# FPGA_Configuration_JTAG.net
KiCad netlist of a schematic drawn in Altium Designer
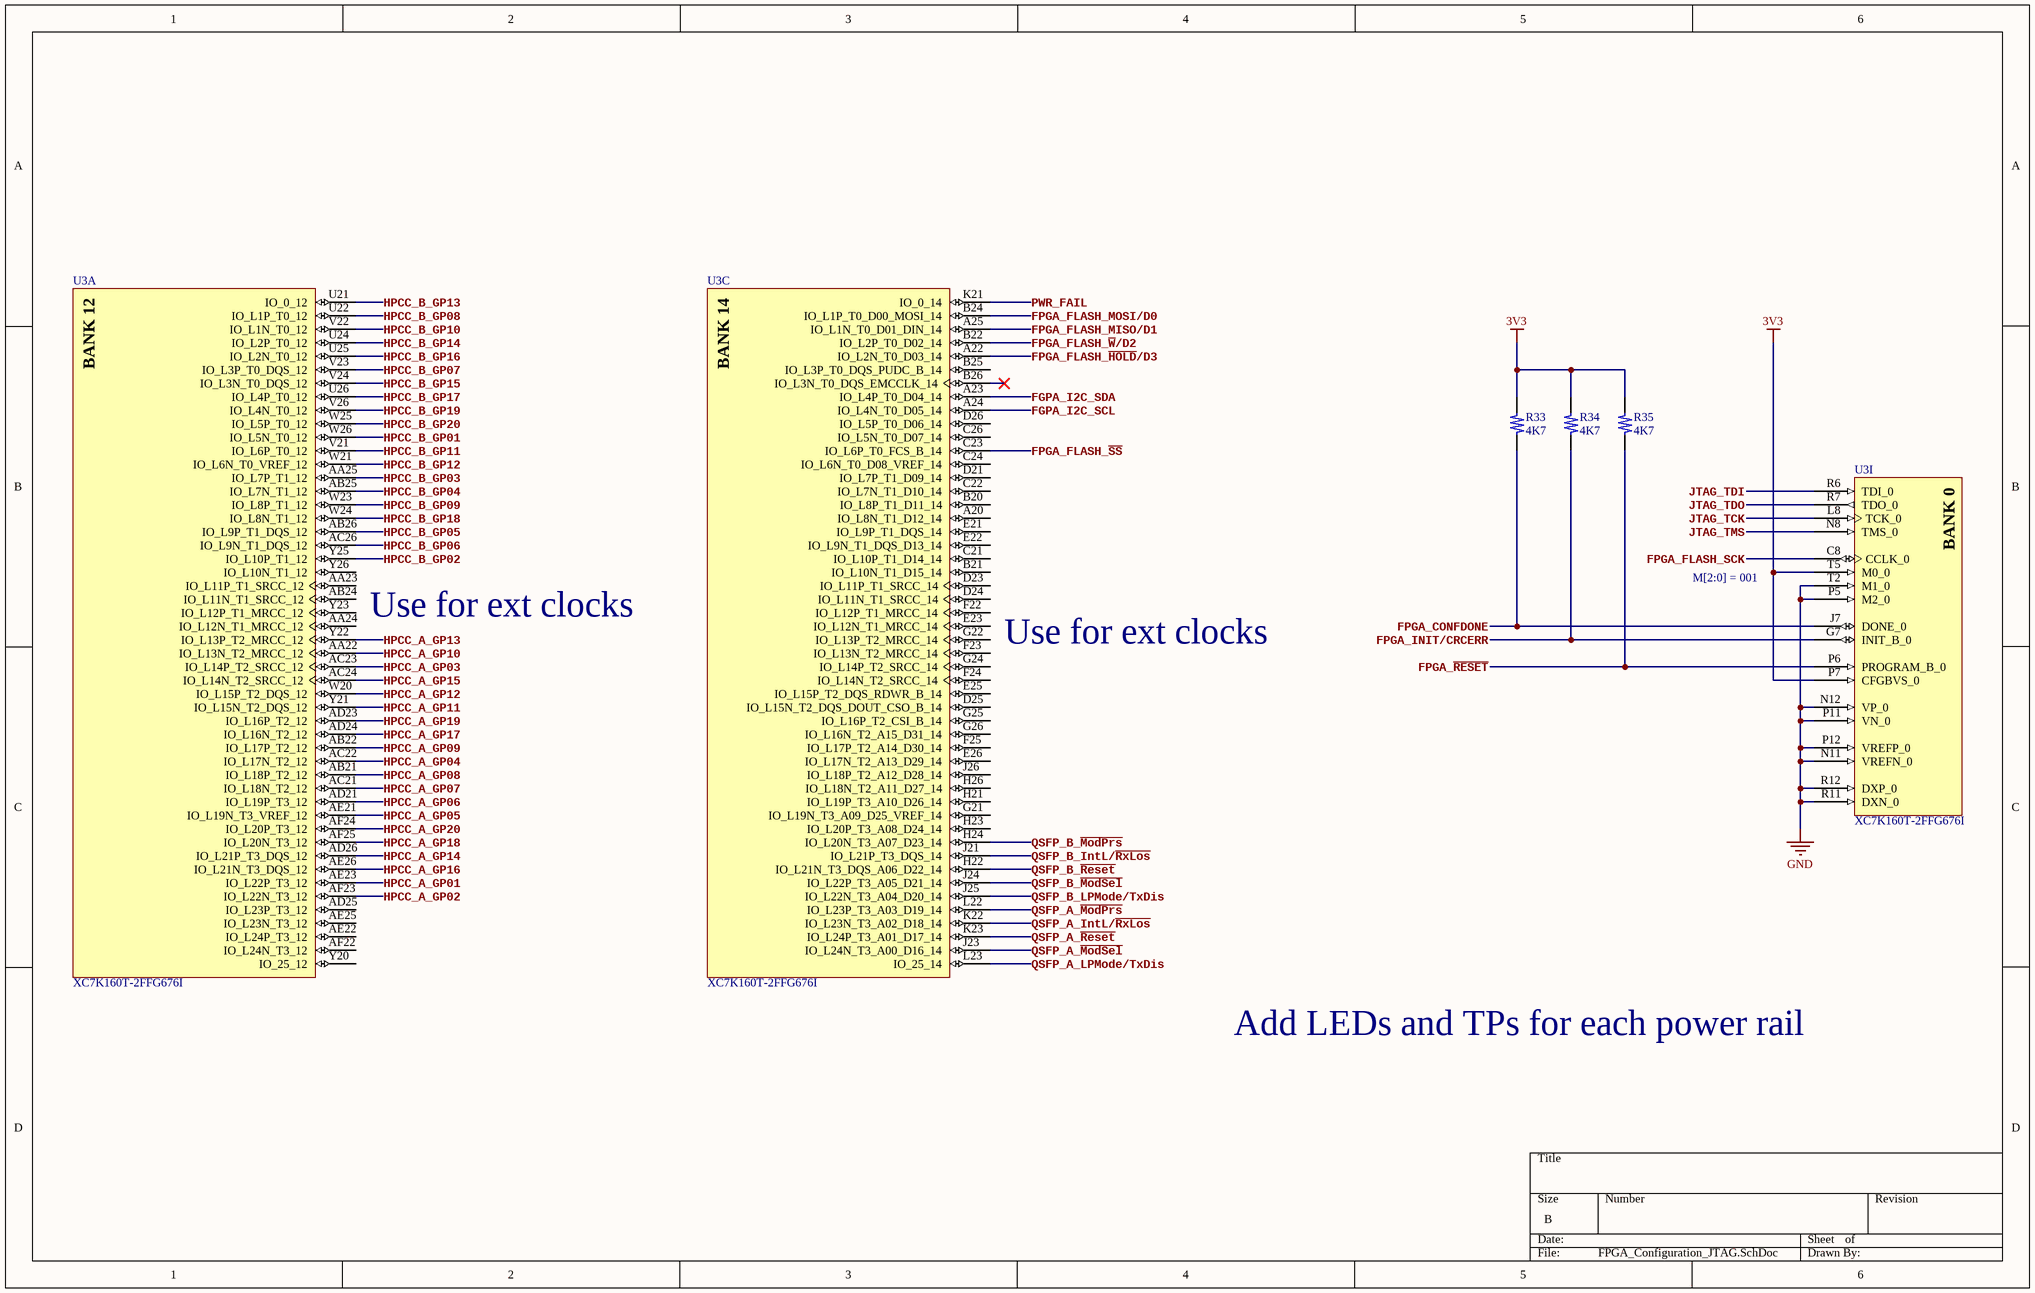
[diagram p0: FPGA_Configuration_JTAG.SchDoc]

(export (version "E")
  (design (tool "Eeschema 10.0.6"))
  (components
    (comp (ref "R33")
      (value "4K7")
      (footprint "R_0402_Generic")
      (description "4.7KOhm 1% 1/10W SMD resistor in 0402 size")
      (fields
        (field (name "MANUFACTURER") "Panasonic")
        (field (name "MANUFACTURER PART NUMBER") "ERJ-2RKF4701X")
      )
      (libsource (lib "Capstone_Schematic_Library") (part "ERJ-2RKF4701X"))
    )
    (comp (ref "R34")
      (value "4K7")
      (footprint "R_0402_Generic")
      (description "4.7KOhm 1% 1/10W SMD resistor in 0402 size")
      (fields
        (field (name "MANUFACTURER") "Panasonic")
        (field (name "MANUFACTURER PART NUMBER") "ERJ-2RKF4701X")
      )
      (libsource (lib "Capstone_Schematic_Library") (part "ERJ-2RKF4701X"))
    )
    (comp (ref "R35")
      (value "4K7")
      (footprint "R_0402_Generic")
      (description "4.7KOhm 1% 1/10W SMD resistor in 0402 size")
      (fields
        (field (name "MANUFACTURER") "Panasonic")
        (field (name "MANUFACTURER PART NUMBER") "ERJ-2RKF4701X")
      )
      (libsource (lib "Capstone_Schematic_Library") (part "ERJ-2RKF4701X"))
    )
    (comp (ref "U3")
      (value "XC7K160T-2FFG676I")
      (footprint "FFG676_(XC7K160T-2FFG676I)")
      (description "Kintex-7 FPGA, 400 User I/Os, 8 GTX, 676-Ball BGA, Speed Grade 2, Industrial Grade, Pb-Free")
      (fields (field (name "MANUFACTURER") "AMD/Xilinx"))
      (libsource (lib "Capstone_Schematic_Library") (part "XC7K160T"))
    )
  )
  (nets
    (net (code "1") (name "/FGPA_I2C_SCL") (class "Default")
      (node (ref "U3") (pin "A24") (pinfunction "IO_L4N_T0_D05_14_A24") (pintype "bidirectional"))
    )
    (net (code "2") (name "/FGPA_I2C_SDA") (class "Default")
      (node (ref "U3") (pin "A23") (pinfunction "IO_L4P_T0_D04_14_A23") (pintype "bidirectional"))
    )
    (net (code "3") (name "/FPGA_CONFDONE") (class "Default")
      (node (ref "R33") (pin "1") (pinfunction "1_1") (pintype "passive"))
      (node (ref "U3") (pin "J7") (pinfunction "DONE_0_J7") (pintype "bidirectional"))
    )
    (net (code "4") (name "/FPGA_FLASH_MISO{slash}D1") (class "Default")
      (node (ref "U3") (pin "A25") (pinfunction "IO_L1N_T0_D01_DIN_14_A25") (pintype "bidirectional"))
    )
    (net (code "5") (name "/FPGA_FLASH_MOSI{slash}D0") (class "Default")
      (node (ref "U3") (pin "B24") (pinfunction "IO_L1P_T0_D00_MOSI_14_B24") (pintype "bidirectional"))
    )
    (net (code "6") (name "/FPGA_FLASH_SCK") (class "Default")
      (node (ref "U3") (pin "C8") (pinfunction "CCLK_0_C8") (pintype "bidirectional"))
    )
    (net (code "7") (name "/FPGA_FLASH_~{HOLD}{slash}D3") (class "Default")
      (node (ref "U3") (pin "A22") (pinfunction "IO_L2N_T0_D03_14_A22") (pintype "bidirectional"))
    )
    (net (code "8") (name "/FPGA_FLASH_~{SS}") (class "Default")
      (node (ref "U3") (pin "C23") (pinfunction "IO_L6P_T0_FCS_B_14_C23") (pintype "bidirectional"))
    )
    (net (code "9") (name "/FPGA_FLASH_~{W}{slash}D2") (class "Default")
      (node (ref "U3") (pin "B22") (pinfunction "IO_L2P_T0_D02_14_B22") (pintype "bidirectional"))
    )
    (net (code "10") (name "/FPGA_INIT{slash}CRCERR") (class "Default")
      (node (ref "R34") (pin "1") (pinfunction "1_1") (pintype "passive"))
      (node (ref "U3") (pin "G7") (pinfunction "INIT_B_0_G7") (pintype "bidirectional"))
    )
    (net (code "11") (name "/FPGA_~{RESET}") (class "Default")
      (node (ref "R35") (pin "1") (pinfunction "1_1") (pintype "passive"))
      (node (ref "U3") (pin "P6") (pinfunction "PROGRAM_B_0_P6") (pintype "input"))
    )
    (net (code "12") (name "/HPCC_A_GP01") (class "Default")
      (node (ref "U3") (pin "AE23") (pinfunction "IO_L22P_T3_12_AE23") (pintype "bidirectional"))
    )
    (net (code "13") (name "/HPCC_A_GP02") (class "Default")
      (node (ref "U3") (pin "AF23") (pinfunction "IO_L22N_T3_12_AF23") (pintype "bidirectional"))
    )
    (net (code "14") (name "/HPCC_A_GP03") (class "Default")
      (node (ref "U3") (pin "AC23") (pinfunction "IO_L14P_T2_SRCC_12_AC23") (pintype "bidirectional"))
    )
    (net (code "15") (name "/HPCC_A_GP04") (class "Default")
      (node (ref "U3") (pin "AC22") (pinfunction "IO_L17N_T2_12_AC22") (pintype "bidirectional"))
    )
    (net (code "16") (name "/HPCC_A_GP05") (class "Default")
      (node (ref "U3") (pin "AE21") (pinfunction "IO_L19N_T3_VREF_12_AE21") (pintype "bidirectional"))
    )
    (net (code "17") (name "/HPCC_A_GP06") (class "Default")
      (node (ref "U3") (pin "AD21") (pinfunction "IO_L19P_T3_12_AD21") (pintype "bidirectional"))
    )
    (net (code "18") (name "/HPCC_A_GP07") (class "Default")
      (node (ref "U3") (pin "AC21") (pinfunction "IO_L18N_T2_12_AC21") (pintype "bidirectional"))
    )
    (net (code "19") (name "/HPCC_A_GP08") (class "Default")
      (node (ref "U3") (pin "AB21") (pinfunction "IO_L18P_T2_12_AB21") (pintype "bidirectional"))
    )
    (net (code "20") (name "/HPCC_A_GP09") (class "Default")
      (node (ref "U3") (pin "AB22") (pinfunction "IO_L17P_T2_12_AB22") (pintype "bidirectional"))
    )
    (net (code "21") (name "/HPCC_A_GP10") (class "Default")
      (node (ref "U3") (pin "AA22") (pinfunction "IO_L13N_T2_MRCC_12_AA22") (pintype "bidirectional"))
    )
    (net (code "22") (name "/HPCC_A_GP11") (class "Default")
      (node (ref "U3") (pin "Y21") (pinfunction "IO_L15N_T2_DQS_12_Y21") (pintype "bidirectional"))
    )
    (net (code "23") (name "/HPCC_A_GP12") (class "Default")
      (node (ref "U3") (pin "W20") (pinfunction "IO_L15P_T2_DQS_12_W20") (pintype "bidirectional"))
    )
    (net (code "24") (name "/HPCC_A_GP13") (class "Default")
      (node (ref "U3") (pin "Y22") (pinfunction "IO_L13P_T2_MRCC_12_Y22") (pintype "bidirectional"))
    )
    (net (code "25") (name "/HPCC_A_GP14") (class "Default")
      (node (ref "U3") (pin "AD26") (pinfunction "IO_L21P_T3_DQS_12_AD26") (pintype "bidirectional"))
    )
    (net (code "26") (name "/HPCC_A_GP15") (class "Default")
      (node (ref "U3") (pin "AC24") (pinfunction "IO_L14N_T2_SRCC_12_AC24") (pintype "bidirectional"))
    )
    (net (code "27") (name "/HPCC_A_GP16") (class "Default")
      (node (ref "U3") (pin "AE26") (pinfunction "IO_L21N_T3_DQS_12_AE26") (pintype "bidirectional"))
    )
    (net (code "28") (name "/HPCC_A_GP17") (class "Default")
      (node (ref "U3") (pin "AD24") (pinfunction "IO_L16N_T2_12_AD24") (pintype "bidirectional"))
    )
    (net (code "29") (name "/HPCC_A_GP18") (class "Default")
      (node (ref "U3") (pin "AF25") (pinfunction "IO_L20N_T3_12_AF25") (pintype "bidirectional"))
    )
    (net (code "30") (name "/HPCC_A_GP19") (class "Default")
      (node (ref "U3") (pin "AD23") (pinfunction "IO_L16P_T2_12_AD23") (pintype "bidirectional"))
    )
    (net (code "31") (name "/HPCC_A_GP20") (class "Default")
      (node (ref "U3") (pin "AF24") (pinfunction "IO_L20P_T3_12_AF24") (pintype "bidirectional"))
    )
    (net (code "32") (name "/HPCC_B_GP01") (class "Default")
      (node (ref "U3") (pin "W26") (pinfunction "IO_L5N_T0_12_W26") (pintype "bidirectional"))
    )
    (net (code "33") (name "/HPCC_B_GP02") (class "Default")
      (node (ref "U3") (pin "Y25") (pinfunction "IO_L10P_T1_12_Y25") (pintype "bidirectional"))
    )
    (net (code "34") (name "/HPCC_B_GP03") (class "Default")
      (node (ref "U3") (pin "AA25") (pinfunction "IO_L7P_T1_12_AA25") (pintype "bidirectional"))
    )
    (net (code "35") (name "/HPCC_B_GP04") (class "Default")
      (node (ref "U3") (pin "AB25") (pinfunction "IO_L7N_T1_12_AB25") (pintype "bidirectional"))
    )
    (net (code "36") (name "/HPCC_B_GP05") (class "Default")
      (node (ref "U3") (pin "AB26") (pinfunction "IO_L9P_T1_DQS_12_AB26") (pintype "bidirectional"))
    )
    (net (code "37") (name "/HPCC_B_GP06") (class "Default")
      (node (ref "U3") (pin "AC26") (pinfunction "IO_L9N_T1_DQS_12_AC26") (pintype "bidirectional"))
    )
    (net (code "38") (name "/HPCC_B_GP07") (class "Default")
      (node (ref "U3") (pin "V23") (pinfunction "IO_L3P_T0_DQS_12_V23") (pintype "bidirectional"))
    )
    (net (code "39") (name "/HPCC_B_GP08") (class "Default")
      (node (ref "U3") (pin "U22") (pinfunction "IO_L1P_T0_12_U22") (pintype "bidirectional"))
    )
    (net (code "40") (name "/HPCC_B_GP09") (class "Default")
      (node (ref "U3") (pin "W23") (pinfunction "IO_L8P_T1_12_W23") (pintype "bidirectional"))
    )
    (net (code "41") (name "/HPCC_B_GP10") (class "Default")
      (node (ref "U3") (pin "V22") (pinfunction "IO_L1N_T0_12_V22") (pintype "bidirectional"))
    )
    (net (code "42") (name "/HPCC_B_GP11") (class "Default")
      (node (ref "U3") (pin "V21") (pinfunction "IO_L6P_T0_12_V21") (pintype "bidirectional"))
    )
    (net (code "43") (name "/HPCC_B_GP12") (class "Default")
      (node (ref "U3") (pin "W21") (pinfunction "IO_L6N_T0_VREF_12_W21") (pintype "bidirectional"))
    )
    (net (code "44") (name "/HPCC_B_GP13") (class "Default")
      (node (ref "U3") (pin "U21") (pinfunction "IO_0_12_U21") (pintype "bidirectional"))
    )
    (net (code "45") (name "/HPCC_B_GP14") (class "Default")
      (node (ref "U3") (pin "U24") (pinfunction "IO_L2P_T0_12_U24") (pintype "bidirectional"))
    )
    (net (code "46") (name "/HPCC_B_GP15") (class "Default")
      (node (ref "U3") (pin "V24") (pinfunction "IO_L3N_T0_DQS_12_V24") (pintype "bidirectional"))
    )
    (net (code "47") (name "/HPCC_B_GP16") (class "Default")
      (node (ref "U3") (pin "U25") (pinfunction "IO_L2N_T0_12_U25") (pintype "bidirectional"))
    )
    (net (code "48") (name "/HPCC_B_GP17") (class "Default")
      (node (ref "U3") (pin "U26") (pinfunction "IO_L4P_T0_12_U26") (pintype "bidirectional"))
    )
    (net (code "49") (name "/HPCC_B_GP18") (class "Default")
      (node (ref "U3") (pin "W24") (pinfunction "IO_L8N_T1_12_W24") (pintype "bidirectional"))
    )
    (net (code "50") (name "/HPCC_B_GP19") (class "Default")
      (node (ref "U3") (pin "V26") (pinfunction "IO_L4N_T0_12_V26") (pintype "bidirectional"))
    )
    (net (code "51") (name "/HPCC_B_GP20") (class "Default")
      (node (ref "U3") (pin "W25") (pinfunction "IO_L5P_T0_12_W25") (pintype "bidirectional"))
    )
    (net (code "52") (name "/JTAG_TCK") (class "Default")
      (node (ref "U3") (pin "L8") (pinfunction "TCK_0_L8") (pintype "input"))
    )
    (net (code "53") (name "/JTAG_TDI") (class "Default")
      (node (ref "U3") (pin "R6") (pinfunction "TDI_0_R6") (pintype "input"))
    )
    (net (code "54") (name "/JTAG_TDO") (class "Default")
      (node (ref "U3") (pin "R7") (pinfunction "TDO_0_R7") (pintype "output"))
    )
    (net (code "55") (name "/JTAG_TMS") (class "Default")
      (node (ref "U3") (pin "N8") (pinfunction "TMS_0_N8") (pintype "input"))
    )
    (net (code "56") (name "/PWR_FAIL") (class "Default")
      (node (ref "U3") (pin "K21") (pinfunction "IO_0_14_K21") (pintype "bidirectional"))
    )
    (net (code "57") (name "/QSFP_A_IntL{slash}~{RxLos}") (class "Default")
      (node (ref "U3") (pin "K22") (pinfunction "IO_L23N_T3_A02_D18_14_K22") (pintype "bidirectional"))
    )
    (net (code "58") (name "/QSFP_A_LPMode{slash}TxDis") (class "Default")
      (node (ref "U3") (pin "L23") (pinfunction "IO_25_14_L23") (pintype "bidirectional"))
    )
    (net (code "59") (name "/QSFP_A_~{ModPrs}") (class "Default")
      (node (ref "U3") (pin "L22") (pinfunction "IO_L23P_T3_A03_D19_14_L22") (pintype "bidirectional"))
    )
    (net (code "60") (name "/QSFP_A_~{ModSel}") (class "Default")
      (node (ref "U3") (pin "J23") (pinfunction "IO_L24N_T3_A00_D16_14_J23") (pintype "bidirectional"))
    )
    (net (code "61") (name "/QSFP_A_~{Reset}") (class "Default")
      (node (ref "U3") (pin "K23") (pinfunction "IO_L24P_T3_A01_D17_14_K23") (pintype "bidirectional"))
    )
    (net (code "62") (name "/QSFP_B_IntL{slash}~{RxLos}") (class "Default")
      (node (ref "U3") (pin "J21") (pinfunction "IO_L21P_T3_DQS_14_J21") (pintype "bidirectional"))
    )
    (net (code "63") (name "/QSFP_B_LPMode{slash}TxDis") (class "Default")
      (node (ref "U3") (pin "J25") (pinfunction "IO_L22N_T3_A04_D20_14_J25") (pintype "bidirectional"))
    )
    (net (code "64") (name "/QSFP_B_~{ModPrs}") (class "Default")
      (node (ref "U3") (pin "H24") (pinfunction "IO_L20N_T3_A07_D23_14_H24") (pintype "bidirectional"))
    )
    (net (code "65") (name "/QSFP_B_~{ModSel}") (class "Default")
      (node (ref "U3") (pin "J24") (pinfunction "IO_L22P_T3_A05_D21_14_J24") (pintype "bidirectional"))
    )
    (net (code "66") (name "/QSFP_B_~{Reset}") (class "Default")
      (node (ref "U3") (pin "H22") (pinfunction "IO_L21N_T3_DQS_A06_D22_14_H22") (pintype "bidirectional"))
    )
    (net (code "67") (name "3V3") (class "Default")
      (node (ref "R33") (pin "2") (pinfunction "2_2") (pintype "passive"))
      (node (ref "R34") (pin "2") (pinfunction "2_2") (pintype "passive"))
      (node (ref "R35") (pin "2") (pinfunction "2_2") (pintype "passive"))
      (node (ref "U3") (pin "P7") (pinfunction "CFGBVS_0_P7") (pintype "input"))
      (node (ref "U3") (pin "T5") (pinfunction "M0_0_T5") (pintype "input"))
    )
    (net (code "68") (name "GND") (class "Default")
      (node (ref "U3") (pin "N11") (pinfunction "VREFN_0_N11") (pintype "input"))
      (node (ref "U3") (pin "N12") (pinfunction "VP_0_N12") (pintype "input"))
      (node (ref "U3") (pin "P11") (pinfunction "VN_0_P11") (pintype "input"))
      (node (ref "U3") (pin "P12") (pinfunction "VREFP_0_P12") (pintype "input"))
      (node (ref "U3") (pin "P5") (pinfunction "M2_0_P5") (pintype "input"))
      (node (ref "U3") (pin "R11") (pinfunction "DXN_0_R11") (pintype "input"))
      (node (ref "U3") (pin "R12") (pinfunction "DXP_0_R12") (pintype "input"))
      (node (ref "U3") (pin "T2") (pinfunction "M1_0_T2") (pintype "input"))
    )
    (net (code "69") (name "unconnected-(U3A-IO_25_12-PadY20)") (class "Default")
      (node (ref "U3") (pin "Y20") (pinfunction "IO_25_12_Y20") (pintype "bidirectional"))
    )
    (net (code "70") (name "unconnected-(U3A-IO_L10N_T1_12-PadY26)") (class "Default")
      (node (ref "U3") (pin "Y26") (pinfunction "IO_L10N_T1_12_Y26") (pintype "bidirectional"))
    )
    (net (code "71") (name "unconnected-(U3A-IO_L11N_T1_SRCC_12-PadAB24)") (class "Default")
      (node (ref "U3") (pin "AB24") (pinfunction "IO_L11N_T1_SRCC_12_AB24") (pintype "bidirectional"))
    )
    (net (code "72") (name "unconnected-(U3A-IO_L11P_T1_SRCC_12-PadAA23)") (class "Default")
      (node (ref "U3") (pin "AA23") (pinfunction "IO_L11P_T1_SRCC_12_AA23") (pintype "bidirectional"))
    )
    (net (code "73") (name "unconnected-(U3A-IO_L12N_T1_MRCC_12-PadAA24)") (class "Default")
      (node (ref "U3") (pin "AA24") (pinfunction "IO_L12N_T1_MRCC_12_AA24") (pintype "bidirectional"))
    )
    (net (code "74") (name "unconnected-(U3A-IO_L12P_T1_MRCC_12-PadY23)") (class "Default")
      (node (ref "U3") (pin "Y23") (pinfunction "IO_L12P_T1_MRCC_12_Y23") (pintype "bidirectional"))
    )
    (net (code "75") (name "unconnected-(U3A-IO_L23N_T3_12-PadAE25)") (class "Default")
      (node (ref "U3") (pin "AE25") (pinfunction "IO_L23N_T3_12_AE25") (pintype "bidirectional"))
    )
    (net (code "76") (name "unconnected-(U3A-IO_L23P_T3_12-PadAD25)") (class "Default")
      (node (ref "U3") (pin "AD25") (pinfunction "IO_L23P_T3_12_AD25") (pintype "bidirectional"))
    )
    (net (code "77") (name "unconnected-(U3A-IO_L24N_T3_12-PadAF22)") (class "Default")
      (node (ref "U3") (pin "AF22") (pinfunction "IO_L24N_T3_12_AF22") (pintype "bidirectional"))
    )
    (net (code "78") (name "unconnected-(U3A-IO_L24P_T3_12-PadAE22)") (class "Default")
      (node (ref "U3") (pin "AE22") (pinfunction "IO_L24P_T3_12_AE22") (pintype "bidirectional"))
    )
    (net (code "79") (name "unconnected-(U3C-IO_L3N_T0_DQS_EMCCLK_14-PadB26)") (class "Default")
      (node (ref "U3") (pin "B26") (pinfunction "IO_L3N_T0_DQS_EMCCLK_14_B26") (pintype "bidirectional+no_connect"))
    )
    (net (code "80") (name "unconnected-(U3C-IO_L3P_T0_DQS_PUDC_B_14-PadB25)") (class "Default")
      (node (ref "U3") (pin "B25") (pinfunction "IO_L3P_T0_DQS_PUDC_B_14_B25") (pintype "bidirectional"))
    )
    (net (code "81") (name "unconnected-(U3C-IO_L5N_T0_D07_14-PadC26)") (class "Default")
      (node (ref "U3") (pin "C26") (pinfunction "IO_L5N_T0_D07_14_C26") (pintype "bidirectional"))
    )
    (net (code "82") (name "unconnected-(U3C-IO_L5P_T0_D06_14-PadD26)") (class "Default")
      (node (ref "U3") (pin "D26") (pinfunction "IO_L5P_T0_D06_14_D26") (pintype "bidirectional"))
    )
    (net (code "83") (name "unconnected-(U3C-IO_L6N_T0_D08_VREF_14-PadC24)") (class "Default")
      (node (ref "U3") (pin "C24") (pinfunction "IO_L6N_T0_D08_VREF_14_C24") (pintype "bidirectional"))
    )
    (net (code "84") (name "unconnected-(U3C-IO_L7N_T1_D10_14-PadC22)") (class "Default")
      (node (ref "U3") (pin "C22") (pinfunction "IO_L7N_T1_D10_14_C22") (pintype "bidirectional"))
    )
    (net (code "85") (name "unconnected-(U3C-IO_L7P_T1_D09_14-PadD21)") (class "Default")
      (node (ref "U3") (pin "D21") (pinfunction "IO_L7P_T1_D09_14_D21") (pintype "bidirectional"))
    )
    (net (code "86") (name "unconnected-(U3C-IO_L8N_T1_D12_14-PadA20)") (class "Default")
      (node (ref "U3") (pin "A20") (pinfunction "IO_L8N_T1_D12_14_A20") (pintype "bidirectional"))
    )
    (net (code "87") (name "unconnected-(U3C-IO_L8P_T1_D11_14-PadB20)") (class "Default")
      (node (ref "U3") (pin "B20") (pinfunction "IO_L8P_T1_D11_14_B20") (pintype "bidirectional"))
    )
    (net (code "88") (name "unconnected-(U3C-IO_L9N_T1_DQS_D13_14-PadE22)") (class "Default")
      (node (ref "U3") (pin "E22") (pinfunction "IO_L9N_T1_DQS_D13_14_E22") (pintype "bidirectional"))
    )
    (net (code "89") (name "unconnected-(U3C-IO_L9P_T1_DQS_14-PadE21)") (class "Default")
      (node (ref "U3") (pin "E21") (pinfunction "IO_L9P_T1_DQS_14_E21") (pintype "bidirectional"))
    )
    (net (code "90") (name "unconnected-(U3C-IO_L10N_T1_D15_14-PadB21)") (class "Default")
      (node (ref "U3") (pin "B21") (pinfunction "IO_L10N_T1_D15_14_B21") (pintype "bidirectional"))
    )
    (net (code "91") (name "unconnected-(U3C-IO_L10P_T1_D14_14-PadC21)") (class "Default")
      (node (ref "U3") (pin "C21") (pinfunction "IO_L10P_T1_D14_14_C21") (pintype "bidirectional"))
    )
    (net (code "92") (name "unconnected-(U3C-IO_L11N_T1_SRCC_14-PadD24)") (class "Default")
      (node (ref "U3") (pin "D24") (pinfunction "IO_L11N_T1_SRCC_14_D24") (pintype "bidirectional"))
    )
    (net (code "93") (name "unconnected-(U3C-IO_L11P_T1_SRCC_14-PadD23)") (class "Default")
      (node (ref "U3") (pin "D23") (pinfunction "IO_L11P_T1_SRCC_14_D23") (pintype "bidirectional"))
    )
    (net (code "94") (name "unconnected-(U3C-IO_L12N_T1_MRCC_14-PadE23)") (class "Default")
      (node (ref "U3") (pin "E23") (pinfunction "IO_L12N_T1_MRCC_14_E23") (pintype "bidirectional"))
    )
    (net (code "95") (name "unconnected-(U3C-IO_L12P_T1_MRCC_14-PadF22)") (class "Default")
      (node (ref "U3") (pin "F22") (pinfunction "IO_L12P_T1_MRCC_14_F22") (pintype "bidirectional"))
    )
    (net (code "96") (name "unconnected-(U3C-IO_L13N_T2_MRCC_14-PadF23)") (class "Default")
      (node (ref "U3") (pin "F23") (pinfunction "IO_L13N_T2_MRCC_14_F23") (pintype "bidirectional"))
    )
    (net (code "97") (name "unconnected-(U3C-IO_L13P_T2_MRCC_14-PadG22)") (class "Default")
      (node (ref "U3") (pin "G22") (pinfunction "IO_L13P_T2_MRCC_14_G22") (pintype "bidirectional"))
    )
    (net (code "98") (name "unconnected-(U3C-IO_L14N_T2_SRCC_14-PadF24)") (class "Default")
      (node (ref "U3") (pin "F24") (pinfunction "IO_L14N_T2_SRCC_14_F24") (pintype "bidirectional"))
    )
    (net (code "99") (name "unconnected-(U3C-IO_L14P_T2_SRCC_14-PadG24)") (class "Default")
      (node (ref "U3") (pin "G24") (pinfunction "IO_L14P_T2_SRCC_14_G24") (pintype "bidirectional"))
    )
    (net (code "100") (name "unconnected-(U3C-IO_L15N_T2_DQS_DOUT_CSO_B_14-PadD25)") (class "Default")
      (node (ref "U3") (pin "D25") (pinfunction "IO_L15N_T2_DQS_DOUT_CSO_B_14_D25") (pintype "bidirectional"))
    )
    (net (code "101") (name "unconnected-(U3C-IO_L15P_T2_DQS_RDWR_B_14-PadE25)") (class "Default")
      (node (ref "U3") (pin "E25") (pinfunction "IO_L15P_T2_DQS_RDWR_B_14_E25") (pintype "bidirectional"))
    )
    (net (code "102") (name "unconnected-(U3C-IO_L16N_T2_A15_D31_14-PadG26)") (class "Default")
      (node (ref "U3") (pin "G26") (pinfunction "IO_L16N_T2_A15_D31_14_G26") (pintype "bidirectional"))
    )
    (net (code "103") (name "unconnected-(U3C-IO_L16P_T2_CSI_B_14-PadG25)") (class "Default")
      (node (ref "U3") (pin "G25") (pinfunction "IO_L16P_T2_CSI_B_14_G25") (pintype "bidirectional"))
    )
    (net (code "104") (name "unconnected-(U3C-IO_L17N_T2_A13_D29_14-PadE26)") (class "Default")
      (node (ref "U3") (pin "E26") (pinfunction "IO_L17N_T2_A13_D29_14_E26") (pintype "bidirectional"))
    )
    (net (code "105") (name "unconnected-(U3C-IO_L17P_T2_A14_D30_14-PadF25)") (class "Default")
      (node (ref "U3") (pin "F25") (pinfunction "IO_L17P_T2_A14_D30_14_F25") (pintype "bidirectional"))
    )
    (net (code "106") (name "unconnected-(U3C-IO_L18N_T2_A11_D27_14-PadH26)") (class "Default")
      (node (ref "U3") (pin "H26") (pinfunction "IO_L18N_T2_A11_D27_14_H26") (pintype "bidirectional"))
    )
    (net (code "107") (name "unconnected-(U3C-IO_L18P_T2_A12_D28_14-PadJ26)") (class "Default")
      (node (ref "U3") (pin "J26") (pinfunction "IO_L18P_T2_A12_D28_14_J26") (pintype "bidirectional"))
    )
    (net (code "108") (name "unconnected-(U3C-IO_L19N_T3_A09_D25_VREF_14-PadG21)") (class "Default")
      (node (ref "U3") (pin "G21") (pinfunction "IO_L19N_T3_A09_D25_VREF_14_G21") (pintype "bidirectional"))
    )
    (net (code "109") (name "unconnected-(U3C-IO_L19P_T3_A10_D26_14-PadH21)") (class "Default")
      (node (ref "U3") (pin "H21") (pinfunction "IO_L19P_T3_A10_D26_14_H21") (pintype "bidirectional"))
    )
    (net (code "110") (name "unconnected-(U3C-IO_L20P_T3_A08_D24_14-PadH23)") (class "Default")
      (node (ref "U3") (pin "H23") (pinfunction "IO_L20P_T3_A08_D24_14_H23") (pintype "bidirectional"))
    )
  )
)
